# MCX_Mezzanine.net
KiCad netlist of a schematic drawn in Altium Designer
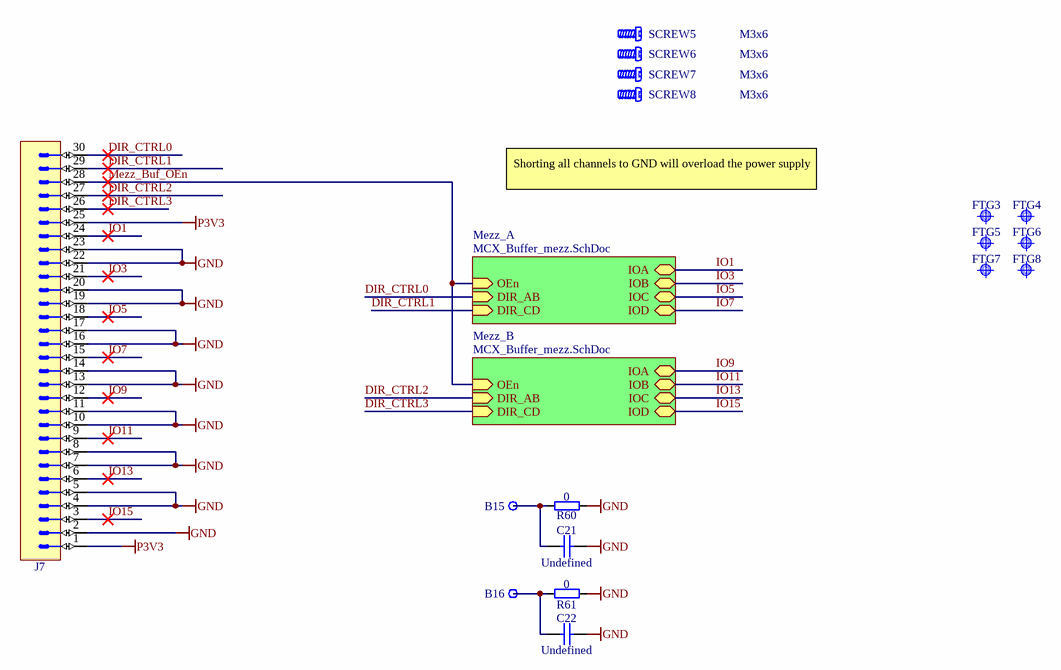
[diagram p0: MCX_Mezzanine.SchDoc]

(export (version "E")
  (design (tool "Eeschema 10.0.6"))
  (components
    (comp (ref "B15")
      (value "Plated Hole")
      (footprint "MTG270_500")
      (description "Single Terminal Socket")
      (fields (field (name "PART NUMBER") "PLATED_HOLE2.7_PAD5.0") (field (name "AUTHOR") "CERN DEM JMW"))
      (libsource (lib "Eletro-mechanical") (part "Single Terminal Socket"))
    )
    (comp (ref "B16")
      (value "Plated Hole")
      (footprint "MTG270_500")
      (description "Single Terminal Socket")
      (fields (field (name "PART NUMBER") "PLATED_HOLE2.7_PAD5.0") (field (name "AUTHOR") "CERN DEM JMW"))
      (libsource (lib "Eletro-mechanical") (part "Single Terminal Socket"))
    )
    (comp (ref "C21")
      (value "Undefined")
      (footprint "CAPC2012X135N")
      (description "Non-polarised capacitor")
      (fields (field (name "PART NUMBER") "CC0805_NO-VALUE") (field (name "AUTHOR") "CERN DEM JLC"))
      (libsource (lib "Capacitors") (part "Capacitor - non polarized"))
    )
    (comp (ref "C22")
      (value "Undefined")
      (footprint "CAPC2012X135N")
      (description "Non-polarised capacitor")
      (fields (field (name "PART NUMBER") "CC0805_NO-VALUE") (field (name "AUTHOR") "CERN DEM JLC"))
      (libsource (lib "Capacitors") (part "Capacitor - non polarized"))
    )
    (comp (ref "FTG3")
      (value "Use only in PCB")
      (footprint "FIDUCIAL_TOP_S100-200")
      (description "Fiducial Target")
      (fields (field (name "PART NUMBER") "FIDUCIAL_TARGET_S100-200") (field (name "AUTHOR") "CERN DEM JLC"))
      (libsource (lib "Eletro-mechanical") (part "Fiducial Target"))
    )
    (comp (ref "FTG4")
      (value "Use only in PCB")
      (footprint "FIDUCIAL_TOP_C100-200")
      (description "Fiducial Target")
      (fields (field (name "PART NUMBER") "FIDUCIAL_TARGET_C100-200") (field (name "AUTHOR") "CERN DEM JLC"))
      (libsource (lib "Eletro-mechanical") (part "Fiducial Target"))
    )
    (comp (ref "FTG5")
      (value "Use only in PCB")
      (footprint "FIDUCIAL_TOP_S100-200")
      (description "Fiducial Target")
      (fields (field (name "PART NUMBER") "FIDUCIAL_TARGET_S100-200") (field (name "AUTHOR") "CERN DEM JLC"))
      (libsource (lib "Eletro-mechanical") (part "Fiducial Target"))
    )
    (comp (ref "FTG6")
      (value "Use only in PCB")
      (footprint "FIDUCIAL_TOP_C100-200")
      (description "Fiducial Target")
      (fields (field (name "PART NUMBER") "FIDUCIAL_TARGET_C100-200") (field (name "AUTHOR") "CERN DEM JLC"))
      (libsource (lib "Eletro-mechanical") (part "Fiducial Target"))
    )
    (comp (ref "FTG7")
      (value "Use only in PCB")
      (footprint "FIDUCIAL_TOP_C100-200")
      (description "Fiducial Target")
      (fields (field (name "PART NUMBER") "FIDUCIAL_TARGET_C100-200") (field (name "AUTHOR") "CERN DEM JLC"))
      (libsource (lib "Eletro-mechanical") (part "Fiducial Target"))
    )
    (comp (ref "FTG8")
      (value "Use only in PCB")
      (footprint "FIDUCIAL_TOP_S100-200")
      (description "Fiducial Target")
      (fields (field (name "PART NUMBER") "FIDUCIAL_TARGET_S100-200") (field (name "AUTHOR") "CERN DEM JLC"))
      (libsource (lib "Eletro-mechanical") (part "Fiducial Target"))
    )
    (comp (ref "J7")
      (value "AMPMODU")
      (footprint "TYCO_1-215307-5")
      (description "Connector 2.54mm, 30 pin female, vertical, 7mm, AMPMODU HV-100/HV-190")
      (fields
        (field (name "PART NUMBER") "TYCO_1-215307-5")
        (field (name "MANUFACTURER") "TYCO ELECTRONICS")
        (field (name "AUTHOR") "GK")
      )
      (libsource (lib "LIBRARY_SCH") (part "CON_2x15_2.54_female_V_mirror"))
    )
    (comp (ref "R60")
      (value "0")
      (footprint "RESC1608X55N")
      (description "Resistor")
      (fields
        (field (name "PART NUMBER") "R0603_0R_JUMPER")
        (field (name "MANUFACTURER") "GENERIC")
        (field (name "AUTHOR") "CERN DEM JLC")
      )
      (libsource (lib "Resistors") (part "Resistor"))
    )
    (comp (ref "R61")
      (value "0")
      (footprint "RESC1608X55N")
      (description "Resistor")
      (fields
        (field (name "PART NUMBER") "R0603_0R_JUMPER")
        (field (name "MANUFACTURER") "GENERIC")
        (field (name "AUTHOR") "CERN DEM JLC")
      )
      (libsource (lib "Resistors") (part "Resistor"))
    )
    (comp (ref "SCREW5")
      (value "M3x6")
      (footprint "BOSSARD_BN5687-3061605_v")
      (description "Screw")
      (fields
        (field (name "PART NUMBER") "BOSSARD_BN5687-3061605_v")
        (field (name "MANUFACTURER") "BOSSARD")
        (field (name "AUTHOR") "CERN DEM JLC")
      )
      (libsource (lib "Eletro-mechanical") (part "Screw"))
    )
    (comp (ref "SCREW6")
      (value "M3x6")
      (footprint "BOSSARD_BN5687-3061605_v")
      (description "Screw")
      (fields
        (field (name "PART NUMBER") "BOSSARD_BN5687-3061605_v")
        (field (name "MANUFACTURER") "BOSSARD")
        (field (name "AUTHOR") "CERN DEM JLC")
      )
      (libsource (lib "Eletro-mechanical") (part "Screw"))
    )
    (comp (ref "SCREW7")
      (value "M3x6")
      (footprint "BOSSARD_BN5687-3061605_v")
      (description "Screw")
      (fields
        (field (name "PART NUMBER") "BOSSARD_BN5687-3061605_v")
        (field (name "MANUFACTURER") "BOSSARD")
        (field (name "AUTHOR") "CERN DEM JLC")
      )
      (libsource (lib "Eletro-mechanical") (part "Screw"))
    )
    (comp (ref "SCREW8")
      (value "M3x6")
      (footprint "BOSSARD_BN5687-3061605_v")
      (description "Screw")
      (fields
        (field (name "PART NUMBER") "BOSSARD_BN5687-3061605_v")
        (field (name "MANUFACTURER") "BOSSARD")
        (field (name "AUTHOR") "CERN DEM JLC")
      )
      (libsource (lib "Eletro-mechanical") (part "Screw"))
    )
  )
  (nets
    (net (code "1") (name "/DIR_CTRL0") (class "Default")
      (node (ref "J7") (pin "30") (pinfunction "30_30") (pintype "bidirectional"))
    )
    (net (code "2") (name "/DIR_CTRL1") (class "Default")
      (node (ref "J7") (pin "29") (pinfunction "29_29") (pintype "bidirectional"))
    )
    (net (code "3") (name "/DIR_CTRL2") (class "Default")
      (node (ref "J7") (pin "27") (pinfunction "27_27") (pintype "bidirectional"))
    )
    (net (code "4") (name "/DIR_CTRL3") (class "Default")
      (node (ref "J7") (pin "26") (pinfunction "26_26") (pintype "bidirectional"))
    )
    (net (code "5") (name "/IO1") (class "Default")
      (node (ref "J7") (pin "24") (pinfunction "24_24") (pintype "bidirectional"))
    )
    (net (code "6") (name "/IO3") (class "Default")
      (node (ref "J7") (pin "21") (pinfunction "21_21") (pintype "bidirectional"))
    )
    (net (code "7") (name "/IO5") (class "Default")
      (node (ref "J7") (pin "18") (pinfunction "18_18") (pintype "bidirectional"))
    )
    (net (code "8") (name "/IO7") (class "Default")
      (node (ref "J7") (pin "15") (pinfunction "15_15") (pintype "bidirectional"))
    )
    (net (code "9") (name "/IO9") (class "Default")
      (node (ref "J7") (pin "12") (pinfunction "12_12") (pintype "bidirectional"))
    )
    (net (code "10") (name "/IO11") (class "Default")
      (node (ref "J7") (pin "9") (pinfunction "9_9") (pintype "bidirectional"))
    )
    (net (code "11") (name "/IO13") (class "Default")
      (node (ref "J7") (pin "6") (pinfunction "6_6") (pintype "bidirectional"))
    )
    (net (code "12") (name "/IO15") (class "Default")
      (node (ref "J7") (pin "3") (pinfunction "3_3") (pintype "bidirectional"))
    )
    (net (code "14") (name "/OEn") (class "Default")
      (node (ref "J7") (pin "28") (pinfunction "28_28") (pintype "bidirectional"))
    )
    (net (code "15") (name "GND") (class "Default")
      (node (ref "C21") (pin "2") (pinfunction "2_2") (pintype "passive"))
      (node (ref "C22") (pin "2") (pinfunction "2_2") (pintype "passive"))
      (node (ref "J7") (pin "10") (pinfunction "10_10") (pintype "bidirectional"))
      (node (ref "J7") (pin "11") (pinfunction "11_11") (pintype "bidirectional"))
      (node (ref "J7") (pin "13") (pinfunction "13_13") (pintype "bidirectional"))
      (node (ref "J7") (pin "14") (pinfunction "14_14") (pintype "bidirectional"))
      (node (ref "J7") (pin "16") (pinfunction "16_16") (pintype "bidirectional"))
      (node (ref "J7") (pin "17") (pinfunction "17_17") (pintype "bidirectional"))
      (node (ref "J7") (pin "19") (pinfunction "19_19") (pintype "bidirectional"))
      (node (ref "J7") (pin "2") (pinfunction "2_2") (pintype "bidirectional"))
      (node (ref "J7") (pin "20") (pinfunction "20_20") (pintype "bidirectional"))
      (node (ref "J7") (pin "22") (pinfunction "22_22") (pintype "bidirectional"))
      (node (ref "J7") (pin "23") (pinfunction "23_23") (pintype "bidirectional"))
      (node (ref "J7") (pin "4") (pinfunction "4_4") (pintype "bidirectional"))
      (node (ref "J7") (pin "5") (pinfunction "5_5") (pintype "bidirectional"))
      (node (ref "J7") (pin "7") (pinfunction "7_7") (pintype "bidirectional"))
      (node (ref "J7") (pin "8") (pinfunction "8_8") (pintype "bidirectional"))
      (node (ref "R60") (pin "1") (pinfunction "1_1") (pintype "passive"))
      (node (ref "R61") (pin "1") (pinfunction "1_1") (pintype "passive"))
    )
    (net (code "16") (name "Net-(B15-Pad1)") (class "Default")
      (node (ref "B15") (pin "1") (pinfunction "1_1") (pintype "bidirectional"))
      (node (ref "C21") (pin "1") (pinfunction "1_1") (pintype "passive"))
      (node (ref "R60") (pin "2") (pinfunction "2_2") (pintype "passive"))
    )
    (net (code "17") (name "Net-(B16-Pad1)") (class "Default")
      (node (ref "B16") (pin "1") (pinfunction "1_1") (pintype "bidirectional"))
      (node (ref "C22") (pin "1") (pinfunction "1_1") (pintype "passive"))
      (node (ref "R61") (pin "2") (pinfunction "2_2") (pintype "passive"))
    )
    (net (code "18") (name "P3V3") (class "Default")
      (node (ref "J7") (pin "1") (pinfunction "1_1") (pintype "bidirectional"))
      (node (ref "J7") (pin "25") (pinfunction "25_25") (pintype "bidirectional"))
    )
  )
)
